# ProPrj_gas_alarm_2025-01-07.net
KiCad netlist of a schematic drawn in EasyEDA Pro
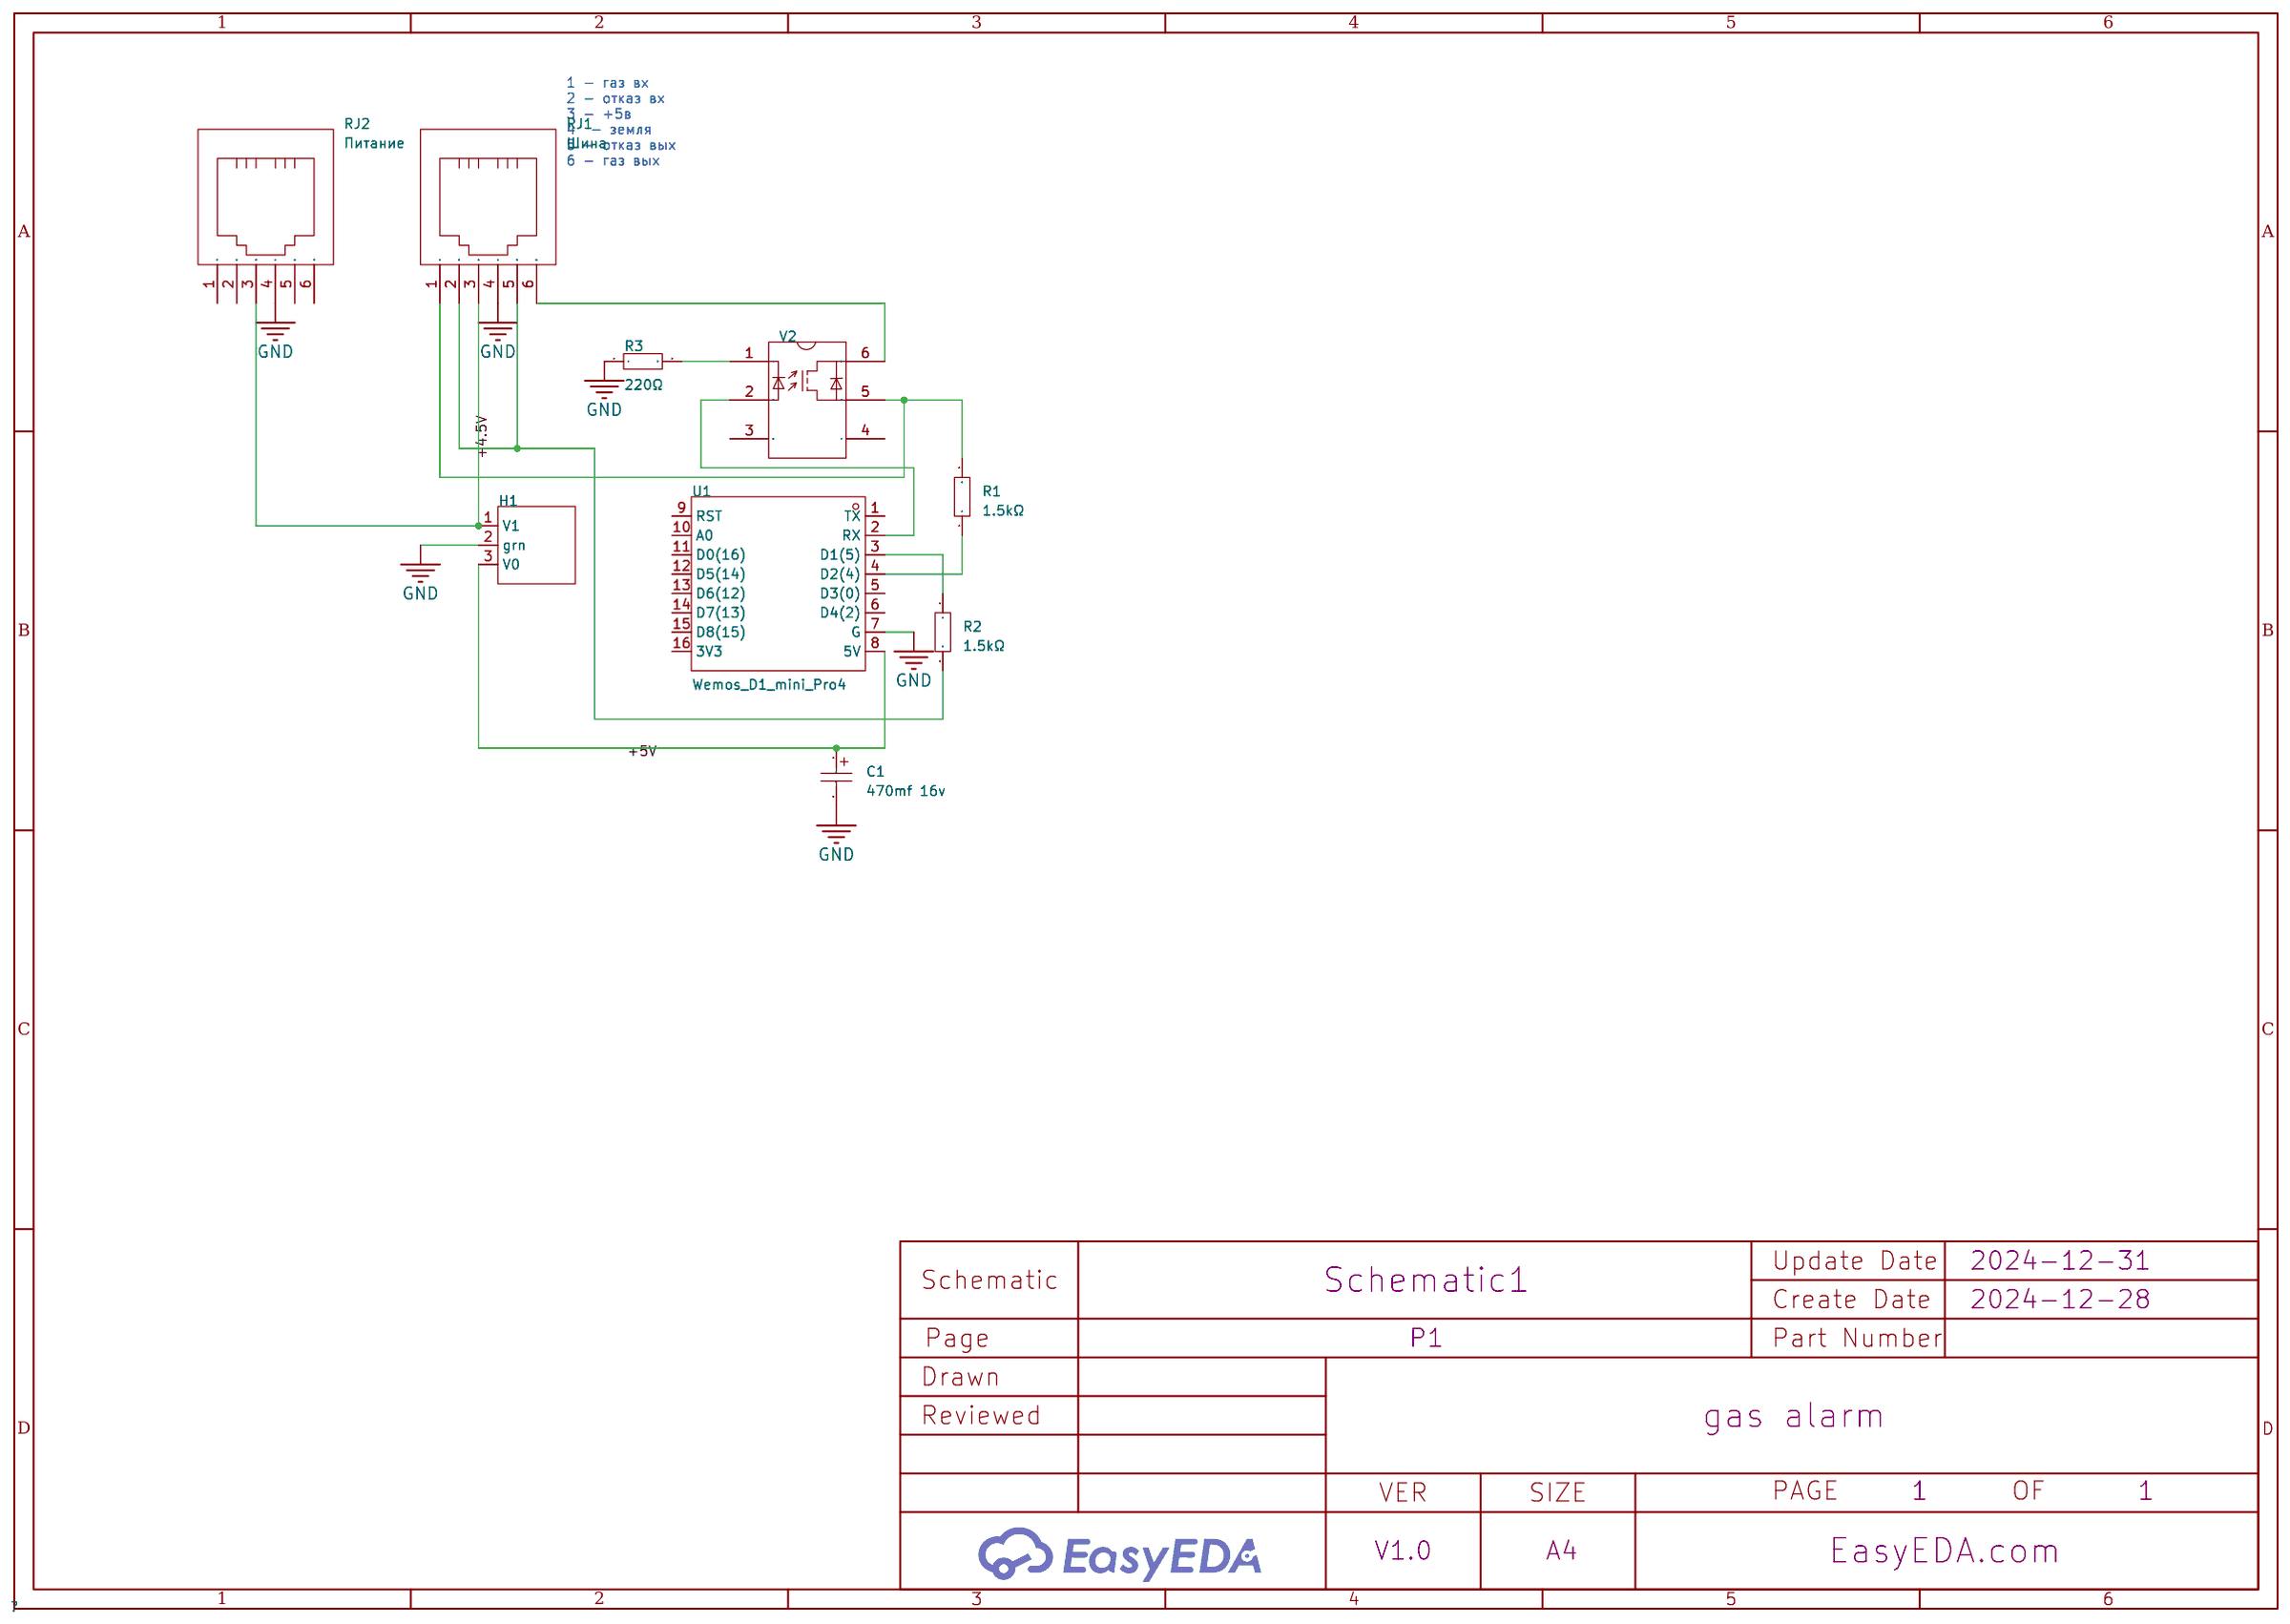
[diagram p0: schematic sheet]

(export (version "E")
  (design (tool "Eeschema 10.0.6"))
  (components
    (comp (ref "C1")
      (value "470mf 16v")
      (footprint "easyedapro:CAP-SMD_BD3.0-L3.3-W3.3-RD")
      (libsource (lib "easyedapro") (part "C_Ele_SMD"))
    )
    (comp (ref "H1")
      (value "~")
      (footprint "easyedapro:HW-626")
      (libsource (lib "easyedapro") (part "HW-6261"))
    )
    (comp (ref "R1")
      (value "1.5kΩ")
      (footprint "easyedapro:RES-TH_BD3.3-L9.0-P13.00-D0.6")
      (libsource (lib "easyedapro") (part "Res"))
    )
    (comp (ref "R2")
      (value "1.5kΩ")
      (footprint "easyedapro:RES-TH_BD3.3-L9.0-P13.00-D0.6")
      (libsource (lib "easyedapro") (part "Res"))
    )
    (comp (ref "R3")
      (value "220Ω")
      (footprint "easyedapro:RES-TH_BD3.3-L9.0-P13.00-D0.6")
      (libsource (lib "easyedapro") (part "Res"))
    )
    (comp (ref "RJ1")
      (value "Шина")
      (footprint "easyedapro:RJ45-TH_KINGHELM_KH-9801-6P6C")
      (fields
        (field (name "Manufacturer Part") "RJ-12 (RJ-25) 6P6C")
        (field (name "Manufacturer") "kinghelm(金航标)")
      )
      (libsource (lib "easyedapro") (part "KH-9801-6P6C"))
    )
    (comp (ref "RJ2")
      (value "Питание")
      (footprint "easyedapro:RJ45-TH_KINGHELM_KH-9801-6P6C")
      (fields
        (field (name "Manufacturer Part") "RJ-12 (RJ-25) 6P6C")
        (field (name "Manufacturer") "kinghelm(金航标)")
      )
      (libsource (lib "easyedapro") (part "KH-9801-6P6C"))
    )
    (comp (ref "U1")
      (value "Wemos_D1_mini_Pro4")
      (footprint "easyedapro:DIP-16_WEMOS_D1_MINI_PRO4")
      (libsource (lib "easyedapro") (part "WEMOS_D1_MINI_PRO4"))
    )
    (comp (ref "V2")
      (value "~")
      (footprint "easyedapro:DIP6")
      (libsource (lib "easyedapro") (part "KP293KП"))
    )
  )
  (nets
    (net (code "1") (name "/+4.5V") (class "Default")
      (node (ref "H1") (pin "1") (pinfunction "V1_1") (pintype "input"))
      (node (ref "RJ1") (pin "3") (pinfunction "3_3") (pintype "unspecified"))
      (node (ref "RJ2") (pin "3") (pinfunction "3_3") (pintype "unspecified"))
    )
    (net (code "2") (name "/+5V") (class "Default")
      (node (ref "C1") (pin "1") (pinfunction "1_1") (pintype "input"))
      (node (ref "H1") (pin "3") (pinfunction "V0_3") (pintype "input"))
      (node (ref "U1") (pin "8") (pinfunction "5V_8") (pintype "unspecified"))
    )
    (net (code "3") (name "GND") (class "Default")
      (node (ref "C1") (pin "2") (pinfunction "2_2") (pintype "input"))
      (node (ref "H1") (pin "2") (pinfunction "grn_2") (pintype "input"))
      (node (ref "R3") (pin "1") (pinfunction "1_1") (pintype "input"))
      (node (ref "RJ1") (pin "4") (pinfunction "4_4") (pintype "unspecified"))
      (node (ref "RJ2") (pin "4") (pinfunction "4_4") (pintype "unspecified"))
      (node (ref "U1") (pin "7") (pinfunction "G_7") (pintype "unspecified"))
    )
    (net (code "4") (name "Net-(R1-Pad2)") (class "Default")
      (node (ref "R1") (pin "2") (pinfunction "2_2") (pintype "input"))
      (node (ref "RJ1") (pin "1") (pinfunction "1_1") (pintype "unspecified"))
      (node (ref "V2") (pin "5") (pinfunction "5_5") (pintype "input"))
    )
    (net (code "5") (name "Net-(R2-Pad2)") (class "Default")
      (node (ref "R2") (pin "2") (pinfunction "2_2") (pintype "input"))
      (node (ref "RJ1") (pin "2") (pinfunction "2_2") (pintype "unspecified"))
      (node (ref "RJ1") (pin "5") (pinfunction "5_5") (pintype "unspecified"))
    )
    (net (code "6") (name "Net-(R3-Pad2)") (class "Default")
      (node (ref "R3") (pin "2") (pinfunction "2_2") (pintype "input"))
      (node (ref "V2") (pin "1") (pinfunction "1_1") (pintype "input"))
    )
    (net (code "7") (name "Net-(RJ1-Pad6)") (class "Default")
      (node (ref "RJ1") (pin "6") (pinfunction "6_6") (pintype "unspecified"))
      (node (ref "V2") (pin "6") (pinfunction "6_6") (pintype "input"))
    )
    (net (code "8") (name "Net-(U1-D1(5))") (class "Default")
      (node (ref "R2") (pin "1") (pinfunction "1_1") (pintype "input"))
      (node (ref "U1") (pin "3") (pinfunction "D1(5)_3") (pintype "unspecified"))
    )
    (net (code "9") (name "Net-(U1-D2(4))") (class "Default")
      (node (ref "R1") (pin "1") (pinfunction "1_1") (pintype "input"))
      (node (ref "U1") (pin "4") (pinfunction "D2(4)_4") (pintype "unspecified"))
    )
    (net (code "10") (name "Net-(U1-RX)") (class "Default")
      (node (ref "U1") (pin "2") (pinfunction "RX_2") (pintype "unspecified"))
      (node (ref "V2") (pin "2") (pinfunction "2_2") (pintype "input"))
    )
    (net (code "11") (name "unconnected-(RJ2-Pad1)") (class "Default")
      (node (ref "RJ2") (pin "1") (pinfunction "1_1") (pintype "unspecified"))
    )
    (net (code "12") (name "unconnected-(RJ2-Pad2)") (class "Default")
      (node (ref "RJ2") (pin "2") (pinfunction "2_2") (pintype "unspecified"))
    )
    (net (code "13") (name "unconnected-(RJ2-Pad5)") (class "Default")
      (node (ref "RJ2") (pin "5") (pinfunction "5_5") (pintype "unspecified"))
    )
    (net (code "14") (name "unconnected-(RJ2-Pad6)") (class "Default")
      (node (ref "RJ2") (pin "6") (pinfunction "6_6") (pintype "unspecified"))
    )
    (net (code "15") (name "unconnected-(U1-3V3-Pad16)") (class "Default")
      (node (ref "U1") (pin "16") (pinfunction "3V3_16") (pintype "unspecified"))
    )
    (net (code "16") (name "unconnected-(U1-A0-Pad10)") (class "Default")
      (node (ref "U1") (pin "10") (pinfunction "A0_10") (pintype "unspecified"))
    )
    (net (code "17") (name "unconnected-(U1-D0(16)-Pad11)") (class "Default")
      (node (ref "U1") (pin "11") (pinfunction "D0(16)_11") (pintype "unspecified"))
    )
    (net (code "18") (name "unconnected-(U1-D3(0)-Pad5)") (class "Default")
      (node (ref "U1") (pin "5") (pinfunction "D3(0)_5") (pintype "unspecified"))
    )
    (net (code "19") (name "unconnected-(U1-D4(2)-Pad6)") (class "Default")
      (node (ref "U1") (pin "6") (pinfunction "D4(2)_6") (pintype "unspecified"))
    )
    (net (code "20") (name "unconnected-(U1-D5(14)-Pad12)") (class "Default")
      (node (ref "U1") (pin "12") (pinfunction "D5(14)_12") (pintype "unspecified"))
    )
    (net (code "21") (name "unconnected-(U1-D6(12)-Pad13)") (class "Default")
      (node (ref "U1") (pin "13") (pinfunction "D6(12)_13") (pintype "unspecified"))
    )
    (net (code "22") (name "unconnected-(U1-D7(13)-Pad14)") (class "Default")
      (node (ref "U1") (pin "14") (pinfunction "D7(13)_14") (pintype "unspecified"))
    )
    (net (code "23") (name "unconnected-(U1-D8(15)-Pad15)") (class "Default")
      (node (ref "U1") (pin "15") (pinfunction "D8(15)_15") (pintype "unspecified"))
    )
    (net (code "24") (name "unconnected-(U1-RST-Pad9)") (class "Default")
      (node (ref "U1") (pin "9") (pinfunction "RST_9") (pintype "unspecified"))
    )
    (net (code "25") (name "unconnected-(U1-TX-Pad1)") (class "Default")
      (node (ref "U1") (pin "1") (pinfunction "TX_1") (pintype "unspecified"))
    )
    (net (code "26") (name "unconnected-(V2-Pad3)") (class "Default")
      (node (ref "V2") (pin "3") (pinfunction "3_3") (pintype "input"))
    )
    (net (code "27") (name "unconnected-(V2-Pad4)") (class "Default")
      (node (ref "V2") (pin "4") (pinfunction "4_4") (pintype "input"))
    )
  )
)
